# UART_BUFFER.net
KiCad netlist of a schematic drawn in Altium Designer
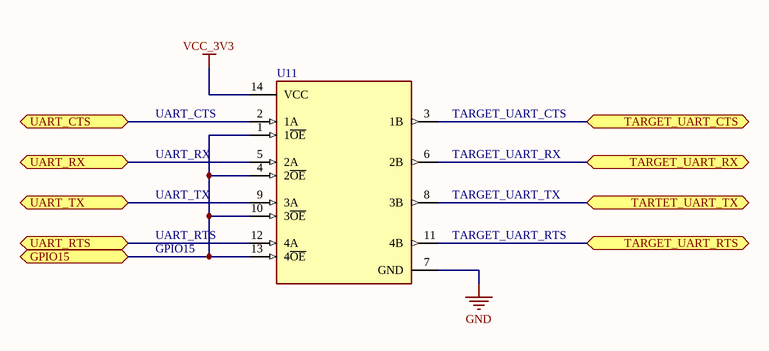
[diagram p0: UART_BUFFER.SchDoc]

(export (version "E")
  (design (tool "Eeschema 10.0.6"))
  (components
    (comp (ref "U11")
      (value "SN74CBTLV3125PWR")
      (footprint "FP-PW0014A-IPC_B")
      (description "IC BUS SWITCH 1 X 1:1 14TSSOP")
      (libsource (lib "Altium Content Vault") (part "3806d98ebe36bc18809b51224d9b5a2"))
    )
  )
  (nets
    (net (code "1") (name "/GPIO15") (class "Default")
      (node (ref "U11") (pin "1") (pinfunction "1~{OE}_1") (pintype "input"))
      (node (ref "U11") (pin "10") (pinfunction "3~{OE}_10") (pintype "input"))
      (node (ref "U11") (pin "13") (pinfunction "4~{OE}_13") (pintype "input"))
      (node (ref "U11") (pin "4") (pinfunction "2~{OE}_4") (pintype "input"))
    )
    (net (code "2") (name "/TARGET_UART_CTS") (class "Default")
      (node (ref "U11") (pin "3") (pinfunction "1B_3") (pintype "output"))
    )
    (net (code "3") (name "/TARGET_UART_RTS") (class "Default")
      (node (ref "U11") (pin "11") (pinfunction "4B_11") (pintype "output"))
    )
    (net (code "4") (name "/TARGET_UART_RX") (class "Default")
      (node (ref "U11") (pin "6") (pinfunction "2B_6") (pintype "output"))
    )
    (net (code "5") (name "/TARTET_UART_TX") (class "Default")
      (node (ref "U11") (pin "8") (pinfunction "3B_8") (pintype "output"))
    )
    (net (code "6") (name "/UART_CTS") (class "Default")
      (node (ref "U11") (pin "2") (pinfunction "1A_2") (pintype "input"))
    )
    (net (code "7") (name "/UART_RTS") (class "Default")
      (node (ref "U11") (pin "12") (pinfunction "4A_12") (pintype "input"))
    )
    (net (code "8") (name "/UART_RX") (class "Default")
      (node (ref "U11") (pin "5") (pinfunction "2A_5") (pintype "input"))
    )
    (net (code "9") (name "/UART_TX") (class "Default")
      (node (ref "U11") (pin "9") (pinfunction "3A_9") (pintype "input"))
    )
    (net (code "10") (name "GND") (class "Default")
      (node (ref "U11") (pin "7") (pinfunction "GND_7") (pintype "power_in"))
    )
    (net (code "11") (name "VCC_3V3") (class "Default")
      (node (ref "U11") (pin "14") (pinfunction "VCC_14") (pintype "power_in"))
    )
  )
)
